# Millable_TitanX1_GPS_Breakout.net
KiCad netlist of a schematic drawn in EAGLE
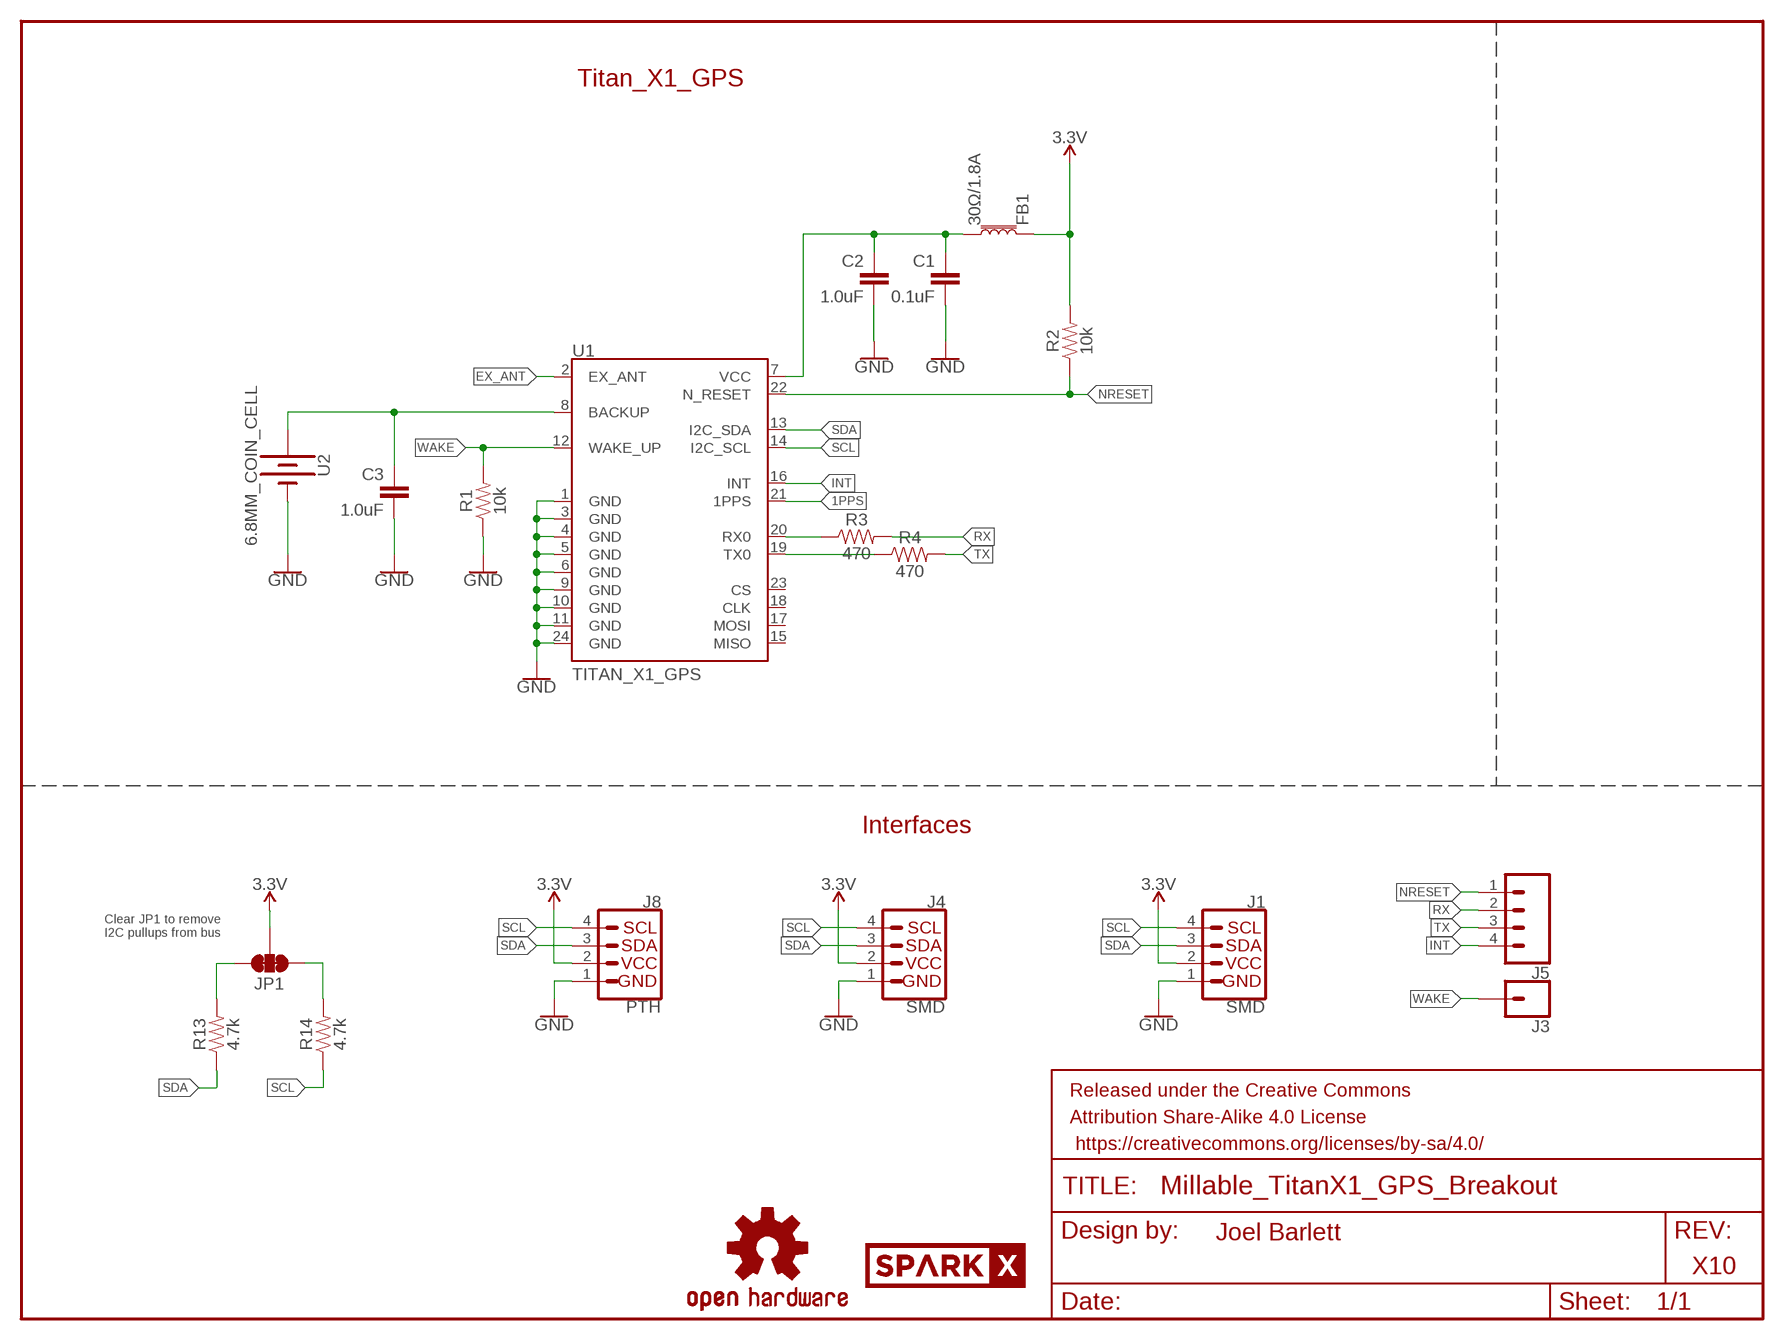
[diagram p0: schematic, sheet 1]

(export (version "E")
  (design (tool "Eeschema 10.0.6"))
  (components
    (comp (ref "C1")
      (value "0.1uF")
      (footprint "eagle-import:0603")
      (libsource (lib "eagle-import") (part "0.1UF-0603-25V-(+80/-20%)"))
    )
    (comp (ref "C2")
      (value "1.0uF")
      (footprint "eagle-import:0603")
      (libsource (lib "eagle-import") (part "1.0UF-0603-16V-10%"))
    )
    (comp (ref "C3")
      (value "1.0uF")
      (footprint "eagle-import:0603")
      (libsource (lib "eagle-import") (part "1.0UF-0603-16V-10%"))
    )
    (comp (ref "FB1")
      (value "30Ω/1.8A")
      (footprint "eagle-import:0603")
      (libsource (lib "eagle-import") (part "FERRITE_BEAD-0603"))
    )
    (comp (ref "FRAME1")
      (value "FRAME-LETTER")
      (footprint "eagle-import:CREATIVE_COMMONS")
      (libsource (lib "eagle-import") (part "FRAME-LETTER"))
    )
    (comp (ref "J1")
      (value "SMD")
      (footprint "eagle-import:1X04_1MM_RA")
      (libsource (lib "eagle-import") (part "I2C_STANDARDJS-1MM"))
    )
    (comp (ref "J3")
      (value "CONN_01PTH_NO_SILK_YES_STOP")
      (footprint "eagle-import:1X01_NO_SILK")
      (libsource (lib "eagle-import") (part "CONN_01PTH_NO_SILK_YES_STOP"))
    )
    (comp (ref "J4")
      (value "SMD")
      (footprint "eagle-import:1X04_1MM_RA")
      (libsource (lib "eagle-import") (part "I2C_STANDARDJS-1MM"))
    )
    (comp (ref "J5")
      (value "CONN_041X04_NO_SILK")
      (footprint "eagle-import:1X04_NO_SILK")
      (libsource (lib "eagle-import") (part "CONN_041X04_NO_SILK"))
    )
    (comp (ref "J8")
      (value "PTH")
      (footprint "eagle-import:1X04_NO_SILK")
      (libsource (lib "eagle-import") (part "I2C_STANDARD_NO_SILK"))
    )
    (comp (ref "JP1")
      (value "JUMPER-SMT_3_2-NC_TRACE_SILK")
      (footprint "eagle-import:SMT-JUMPER_3_2-NC_TRACE_SILK")
      (libsource (lib "eagle-import") (part "JUMPER-SMT_3_2-NC_TRACE_SILK"))
    )
    (comp (ref "LOGO4")
      (value "OSHW-LOGOS")
      (footprint "eagle-import:OSHW-LOGO-S")
      (libsource (lib "eagle-import") (part "OSHW-LOGOS"))
    )
    (comp (ref "R1")
      (value "10k")
      (footprint "eagle-import:0603")
      (libsource (lib "eagle-import") (part "10KOHM-0603-1/10W-1%"))
    )
    (comp (ref "R2")
      (value "10k")
      (footprint "eagle-import:0603")
      (libsource (lib "eagle-import") (part "10KOHM-0603-1/10W-1%"))
    )
    (comp (ref "R3")
      (value "470")
      (footprint "eagle-import:0603")
      (libsource (lib "eagle-import") (part "470OHM-0603-1/10W-1%"))
    )
    (comp (ref "R4")
      (value "470")
      (footprint "eagle-import:0603")
      (libsource (lib "eagle-import") (part "470OHM-0603-1/10W-1%"))
    )
    (comp (ref "R13")
      (value "4.7k")
      (footprint "eagle-import:0603")
      (libsource (lib "eagle-import") (part "4.7KOHM-0603-1/10W-1%"))
    )
    (comp (ref "R14")
      (value "4.7k")
      (footprint "eagle-import:0603")
      (libsource (lib "eagle-import") (part "4.7KOHM-0603-1/10W-1%"))
    )
    (comp (ref "U$1")
      (value "SPARKX-LOGO3")
      (footprint "eagle-import:SPARKX-SMALL")
      (libsource (lib "eagle-import") (part "SPARKX-LOGO3"))
    )
    (comp (ref "U1")
      (value "TITAN_X1_GPS")
      (footprint "eagle-import:TITAN_X1_GPS")
      (libsource (lib "eagle-import") (part "TITAN_X1_GPS"))
    )
    (comp (ref "U2")
      (value "6.8MM_COIN_CELL")
      (footprint "eagle-import:6.8MM_COIN_CELL")
      (libsource (lib "eagle-import") (part "6.8MM_COIN_CELL"))
    )
  )
  (nets
    (net (code "1") (name "1PPS") (class "Default")
      (node (ref "U1") (pin "21") (pinfunction "1PPS_21") (pintype "bidirectional"))
    )
    (net (code "2") (name "3.3V") (class "Default")
      (node (ref "FB1") (pin "1") (pinfunction "1_1") (pintype "passive"))
      (node (ref "J1") (pin "2") (pinfunction "VCC_2") (pintype "power_in"))
      (node (ref "J4") (pin "2") (pinfunction "VCC_2") (pintype "power_in"))
      (node (ref "J8") (pin "2") (pinfunction "2_2") (pintype "power_in"))
      (node (ref "JP1") (pin "2") (pinfunction "2_2") (pintype "passive"))
      (node (ref "R2") (pin "2") (pinfunction "2_2") (pintype "passive"))
    )
    (net (code "3") (name "EX_ANT") (class "Default")
      (node (ref "U1") (pin "2") (pinfunction "EX_ANT_2") (pintype "bidirectional"))
    )
    (net (code "4") (name "GND") (class "Default")
      (node (ref "C1") (pin "2") (pinfunction "2_2") (pintype "passive"))
      (node (ref "C2") (pin "2") (pinfunction "2_2") (pintype "passive"))
      (node (ref "C3") (pin "2") (pinfunction "2_2") (pintype "passive"))
      (node (ref "J1") (pin "1") (pinfunction "GND_1") (pintype "power_in"))
      (node (ref "J4") (pin "1") (pinfunction "GND_1") (pintype "power_in"))
      (node (ref "J8") (pin "1") (pinfunction "1_1") (pintype "power_in"))
      (node (ref "R1") (pin "1") (pinfunction "1_1") (pintype "passive"))
      (node (ref "U1") (pin "1") (pinfunction "GND_1") (pintype "bidirectional"))
      (node (ref "U1") (pin "10") (pinfunction "GND_10") (pintype "bidirectional"))
      (node (ref "U1") (pin "11") (pinfunction "GND_11") (pintype "bidirectional"))
      (node (ref "U1") (pin "24") (pinfunction "GND_24") (pintype "bidirectional"))
      (node (ref "U1") (pin "3") (pinfunction "GND_3") (pintype "bidirectional"))
      (node (ref "U1") (pin "4") (pinfunction "GND_4") (pintype "bidirectional"))
      (node (ref "U1") (pin "5") (pinfunction "GND_5") (pintype "bidirectional"))
      (node (ref "U1") (pin "6") (pinfunction "GND_6") (pintype "bidirectional"))
      (node (ref "U1") (pin "9") (pinfunction "GND_9") (pintype "bidirectional"))
      (node (ref "U2") (pin "-") (pinfunction "-_-") (pintype "power_in"))
    )
    (net (code "5") (name "INT") (class "Default")
      (node (ref "J5") (pin "4") (pinfunction "4_4") (pintype "passive"))
      (node (ref "U1") (pin "16") (pinfunction "INT_16") (pintype "bidirectional"))
    )
    (net (code "6") (name "NRESET") (class "Default")
      (node (ref "J5") (pin "1") (pinfunction "1_1") (pintype "passive"))
      (node (ref "R2") (pin "1") (pinfunction "1_1") (pintype "passive"))
      (node (ref "U1") (pin "22") (pinfunction "N_RESET_22") (pintype "bidirectional"))
    )
    (net (code "7") (name "Net-(JP1-Pad1)") (class "Default")
      (node (ref "JP1") (pin "1") (pinfunction "1_1") (pintype "passive"))
      (node (ref "R14") (pin "2") (pinfunction "2_2") (pintype "passive"))
    )
    (net (code "8") (name "Net-(JP1-Pad3)") (class "Default")
      (node (ref "JP1") (pin "3") (pinfunction "3_3") (pintype "passive"))
      (node (ref "R13") (pin "2") (pinfunction "2_2") (pintype "passive"))
    )
    (net (code "9") (name "Net-(U1-BACKUP)") (class "Default")
      (node (ref "C3") (pin "1") (pinfunction "1_1") (pintype "passive"))
      (node (ref "U1") (pin "8") (pinfunction "BACKUP_8") (pintype "bidirectional"))
      (node (ref "U2") (pin "+") (pinfunction "+_+") (pintype "power_in"))
    )
    (net (code "10") (name "Net-(U1-RX0)") (class "Default")
      (node (ref "R3") (pin "1") (pinfunction "1_1") (pintype "passive"))
      (node (ref "U1") (pin "20") (pinfunction "RX0_20") (pintype "bidirectional"))
    )
    (net (code "11") (name "Net-(U1-TX0)") (class "Default")
      (node (ref "R4") (pin "1") (pinfunction "1_1") (pintype "passive"))
      (node (ref "U1") (pin "19") (pinfunction "TX0_19") (pintype "bidirectional"))
    )
    (net (code "12") (name "Net-(U1-VCC)") (class "Default")
      (node (ref "C1") (pin "1") (pinfunction "1_1") (pintype "passive"))
      (node (ref "C2") (pin "1") (pinfunction "1_1") (pintype "passive"))
      (node (ref "FB1") (pin "2") (pinfunction "2_2") (pintype "passive"))
      (node (ref "U1") (pin "7") (pinfunction "VCC_7") (pintype "bidirectional"))
    )
    (net (code "13") (name "RX") (class "Default")
      (node (ref "J5") (pin "2") (pinfunction "2_2") (pintype "passive"))
      (node (ref "R3") (pin "2") (pinfunction "2_2") (pintype "passive"))
    )
    (net (code "14") (name "SCL") (class "Default")
      (node (ref "J1") (pin "4") (pinfunction "SCL_4") (pintype "passive"))
      (node (ref "J4") (pin "4") (pinfunction "SCL_4") (pintype "passive"))
      (node (ref "J8") (pin "4") (pinfunction "4_4") (pintype "passive"))
      (node (ref "R14") (pin "1") (pinfunction "1_1") (pintype "passive"))
      (node (ref "U1") (pin "14") (pinfunction "I2C_SCL_14") (pintype "bidirectional"))
    )
    (net (code "15") (name "SDA") (class "Default")
      (node (ref "J1") (pin "3") (pinfunction "SDA_3") (pintype "passive"))
      (node (ref "J4") (pin "3") (pinfunction "SDA_3") (pintype "passive"))
      (node (ref "J8") (pin "3") (pinfunction "3_3") (pintype "passive"))
      (node (ref "R13") (pin "1") (pinfunction "1_1") (pintype "passive"))
      (node (ref "U1") (pin "13") (pinfunction "I2C_SDA_13") (pintype "bidirectional"))
    )
    (net (code "16") (name "TX") (class "Default")
      (node (ref "J5") (pin "3") (pinfunction "3_3") (pintype "passive"))
      (node (ref "R4") (pin "2") (pinfunction "2_2") (pintype "passive"))
    )
    (net (code "17") (name "WAKE") (class "Default")
      (node (ref "J3") (pin "1") (pinfunction "1_1") (pintype "passive"))
      (node (ref "R1") (pin "2") (pinfunction "2_2") (pintype "passive"))
      (node (ref "U1") (pin "12") (pinfunction "WAKE_UP_12") (pintype "bidirectional"))
    )
    (net (code "18") (name "unconnected-(U1-CLK-Pad18)") (class "Default")
      (node (ref "U1") (pin "18") (pinfunction "CLK_18") (pintype "bidirectional"))
    )
    (net (code "19") (name "unconnected-(U1-CS-Pad23)") (class "Default")
      (node (ref "U1") (pin "23") (pinfunction "CS_23") (pintype "bidirectional"))
    )
    (net (code "20") (name "unconnected-(U1-MISO-Pad15)") (class "Default")
      (node (ref "U1") (pin "15") (pinfunction "MISO_15") (pintype "bidirectional"))
    )
    (net (code "21") (name "unconnected-(U1-MOSI-Pad17)") (class "Default")
      (node (ref "U1") (pin "17") (pinfunction "MOSI_17") (pintype "bidirectional"))
    )
  )
)
